# 1_P1.net
KiCad netlist of a schematic drawn in Altium Designer
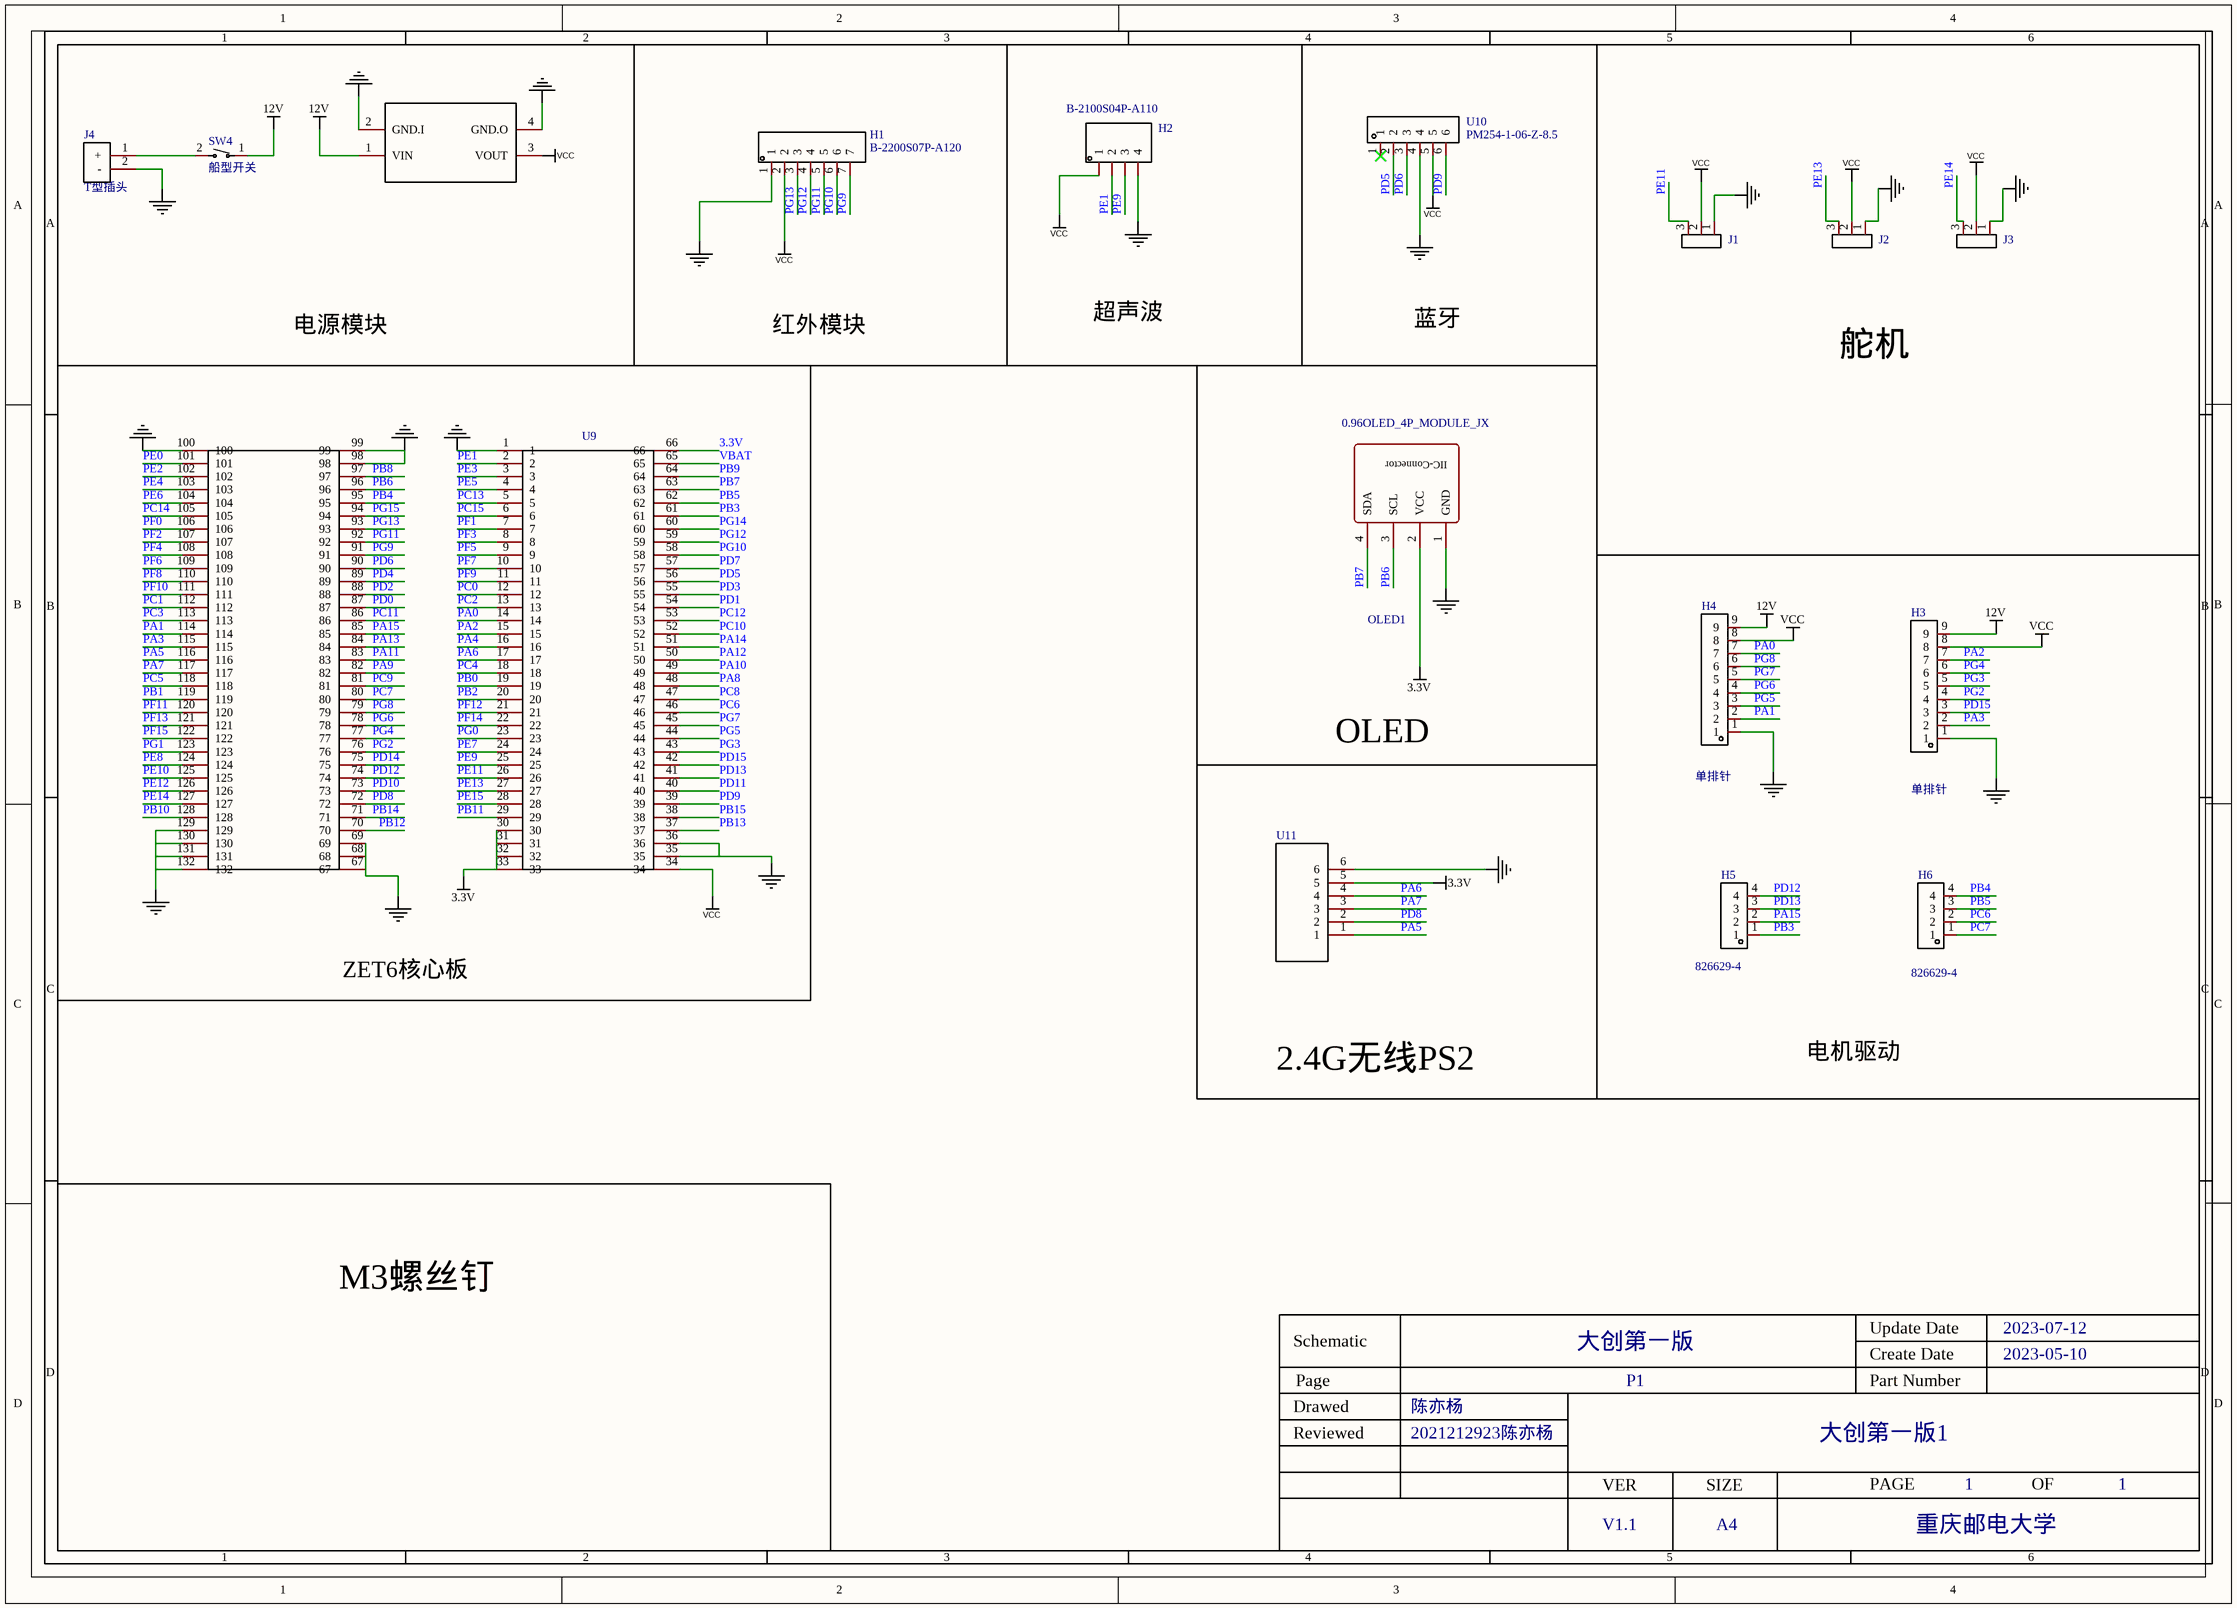
[diagram p0: 1_P1.schdoc]

(export (version "E")
  (design (tool "Eeschema 10.0.6"))
  (components
    (comp (ref "H1")
      (value "B-2200S07P-A120")
      (description "排数:单排;总孔位数:7;间距:2.54mm;插孔结构:1x7P;行距:-;安装类型:直插;塑高:-;触头材质:黄铜;触头镀层:-;")
      (fields (field (name "NAME") "B-2200S07P-A120") (field (name "MANUFACTURER") "Ckmtw(灿科盟)"))
      (libsource (lib "altium-import") (part "root_1_B-2200S07P-A120_"))
    )
    (comp (ref "H2")
      (value "B-2100S04P-A110")
      (fields (field (name "NAME") "B-2100S04P-A110") (field (name "MANUFACTURER") "Ckmtw(灿科盟)"))
      (libsource (lib "altium-import") (part "root_1_B-2100S04P-A110_"))
    )
    (comp (ref "H3")
      (value "单排针")
      (fields (field (name "NAME") "单排针"))
      (libsource (lib "altium-import") (part "root_2_排针9P-2.54MM直插_"))
    )
    (comp (ref "H4")
      (value "单排针")
      (fields (field (name "NAME") "单排针"))
      (libsource (lib "altium-import") (part "root_2_排针9P-2.54MM直插_"))
    )
    (comp (ref "H5")
      (value "826629-4")
      (fields (field (name "NAME") "826629-4") (field (name "MANUFACTURER") "TE Connectivity(美国泰科)"))
      (libsource (lib "altium-import") (part "root_2_排针2_"))
    )
    (comp (ref "H6")
      (value "826629-4")
      (fields (field (name "NAME") "826629-4") (field (name "MANUFACTURER") "TE Connectivity(美国泰科)"))
      (libsource (lib "altium-import") (part "root_2_排针2_"))
    )
    (comp (ref "J1") (value "3排针") (libsource (lib "altium-import") (part "root_2_3排针_")))
    (comp (ref "J2") (value "3排针") (libsource (lib "altium-import") (part "root_2_3排针_")))
    (comp (ref "J3") (value "3排针") (libsource (lib "altium-import") (part "root_2_3排针_")))
    (comp (ref "J4")
      (value "T型插头")
      (fields (field (name "NAME") "T型插头"))
      (libsource (lib "altium-import") (part "root_0_T型插头_"))
    )
    (comp (ref "OLED1")
      (value "0.96OLED_4P_MODULE_JX")
      (fields (field (name "NAME") "0.96OLED_4P_MODULE_JX"))
      (libsource (lib "altium-import") (part "root_3_0.96OLED_4P_MODULE_JX_"))
    )
    (comp (ref "SW4")
      (value "船型开关")
      (description "额定电流:6A;额定电压(AC):250V;额定电压(DC):-;电路结构:单刀双掷;致动器类型:凹面弯曲;致动器颜色:黑色;致动器标志:O-;照明颜色:-;端接样式:焊片;开关功能:开-关;")
      (fields (field (name "NAME") "船型开关") (field (name "MANUFACTURER") "HONGJU(宏聚)"))
      (libsource (lib "altium-import") (part "root_0_mirrored_MR1-110-C5N-BBAA_"))
    )
    (comp (ref "U6") (value "LM2596") (libsource (lib "altium-import") (part "root_0_LM2596_")))
    (comp (ref "U9")
      (value "ZET6核心板")
      (description "F103ZET6核心板")
      (libsource (lib "altium-import") (part "root_0_ZET6核心板_"))
    )
    (comp (ref "U10")
      (value "PM254-1-06-Z-8.5")
      (fields (field (name "NAME") "PM254-1-06-Z-8.5") (field (name "MANUFACTURER") "HCTL(华灿天禄)"))
      (libsource (lib "altium-import") (part "root_1_PM254-1-06-Z-8.5_"))
    )
    (comp (ref "U11") (value "排针1*6") (libsource (lib "altium-import") (part "root_2_排针1*6_")))
  )
  (nets
    (net (code "1") (name "/PA0") (class "Default")
      (node (ref "H4") (pin "7") (pinfunction "7_7") (pintype "passive"))
      (node (ref "U9") (pin "14") (pinfunction "14_14") (pintype "passive"))
    )
    (net (code "2") (name "/PA1") (class "Default")
      (node (ref "H4") (pin "2") (pinfunction "2_2") (pintype "passive"))
      (node (ref "U9") (pin "114") (pinfunction "114_114") (pintype "passive"))
    )
    (net (code "3") (name "/PA2") (class "Default")
      (node (ref "H3") (pin "7") (pinfunction "7_7") (pintype "passive"))
      (node (ref "U9") (pin "15") (pinfunction "15_15") (pintype "passive"))
    )
    (net (code "4") (name "/PA3") (class "Default")
      (node (ref "H3") (pin "2") (pinfunction "2_2") (pintype "passive"))
      (node (ref "U9") (pin "115") (pinfunction "115_115") (pintype "passive"))
    )
    (net (code "5") (name "/PA4") (class "Default")
      (node (ref "U9") (pin "16") (pinfunction "16_16") (pintype "passive"))
    )
    (net (code "6") (name "/PA5") (class "Default")
      (node (ref "U11") (pin "1") (pinfunction "1_1") (pintype "passive"))
      (node (ref "U9") (pin "116") (pinfunction "116_116") (pintype "passive"))
    )
    (net (code "7") (name "/PA6") (class "Default")
      (node (ref "U11") (pin "4") (pinfunction "4_4") (pintype "passive"))
      (node (ref "U9") (pin "17") (pinfunction "17_17") (pintype "passive"))
    )
    (net (code "8") (name "/PA7") (class "Default")
      (node (ref "U11") (pin "3") (pinfunction "3_3") (pintype "passive"))
      (node (ref "U9") (pin "117") (pinfunction "117_117") (pintype "passive"))
    )
    (net (code "9") (name "/PA8") (class "Default")
      (node (ref "U9") (pin "48") (pinfunction "48_48") (pintype "passive"))
    )
    (net (code "10") (name "/PA9") (class "Default")
      (node (ref "U9") (pin "82") (pinfunction "82_82") (pintype "passive"))
    )
    (net (code "11") (name "/PA10") (class "Default")
      (node (ref "U9") (pin "49") (pinfunction "49_49") (pintype "passive"))
    )
    (net (code "12") (name "/PA11") (class "Default")
      (node (ref "U9") (pin "83") (pinfunction "83_83") (pintype "passive"))
    )
    (net (code "13") (name "/PA12") (class "Default")
      (node (ref "U9") (pin "50") (pinfunction "50_50") (pintype "passive"))
    )
    (net (code "14") (name "/PA13") (class "Default")
      (node (ref "U9") (pin "84") (pinfunction "84_84") (pintype "passive"))
    )
    (net (code "15") (name "/PA14") (class "Default")
      (node (ref "U9") (pin "51") (pinfunction "51_51") (pintype "passive"))
    )
    (net (code "16") (name "/PA15") (class "Default")
      (node (ref "H5") (pin "2") (pinfunction "2_2") (pintype "passive"))
      (node (ref "U9") (pin "85") (pinfunction "85_85") (pintype "passive"))
    )
    (net (code "17") (name "/PB0") (class "Default")
      (node (ref "U9") (pin "19") (pinfunction "19_19") (pintype "passive"))
    )
    (net (code "18") (name "/PB1") (class "Default")
      (node (ref "U9") (pin "119") (pinfunction "119_119") (pintype "passive"))
    )
    (net (code "19") (name "/PB2") (class "Default")
      (node (ref "U9") (pin "20") (pinfunction "20_20") (pintype "passive"))
    )
    (net (code "20") (name "/PB3") (class "Default")
      (node (ref "H5") (pin "1") (pinfunction "1_1") (pintype "passive"))
      (node (ref "U9") (pin "61") (pinfunction "61_61") (pintype "passive"))
    )
    (net (code "21") (name "/PB4") (class "Default")
      (node (ref "H6") (pin "4") (pinfunction "4_4") (pintype "passive"))
      (node (ref "U9") (pin "95") (pinfunction "95_95") (pintype "passive"))
    )
    (net (code "22") (name "/PB5") (class "Default")
      (node (ref "H6") (pin "3") (pinfunction "3_3") (pintype "passive"))
      (node (ref "U9") (pin "62") (pinfunction "62_62") (pintype "passive"))
    )
    (net (code "23") (name "/PB6") (class "Default")
      (node (ref "OLED1") (pin "3") (pinfunction "SCL_3") (pintype "passive"))
      (node (ref "U9") (pin "96") (pinfunction "96_96") (pintype "passive"))
    )
    (net (code "24") (name "/PB7") (class "Default")
      (node (ref "OLED1") (pin "4") (pinfunction "SDA_4") (pintype "passive"))
      (node (ref "U9") (pin "63") (pinfunction "63_63") (pintype "passive"))
    )
    (net (code "25") (name "/PB8") (class "Default")
      (node (ref "U9") (pin "97") (pinfunction "97_97") (pintype "passive"))
    )
    (net (code "26") (name "/PB9") (class "Default")
      (node (ref "U9") (pin "64") (pinfunction "64_64") (pintype "passive"))
    )
    (net (code "27") (name "/PB10") (class "Default")
      (node (ref "U9") (pin "128") (pinfunction "128_128") (pintype "passive"))
    )
    (net (code "28") (name "/PB11") (class "Default")
      (node (ref "U9") (pin "29") (pinfunction "29_29") (pintype "passive"))
    )
    (net (code "29") (name "/PB12") (class "Default")
      (node (ref "U9") (pin "70") (pinfunction "70_70") (pintype "passive"))
    )
    (net (code "30") (name "/PB13") (class "Default")
      (node (ref "U9") (pin "37") (pinfunction "37_37") (pintype "passive"))
    )
    (net (code "31") (name "/PB14") (class "Default")
      (node (ref "U9") (pin "71") (pinfunction "71_71") (pintype "passive"))
    )
    (net (code "32") (name "/PB15") (class "Default")
      (node (ref "U9") (pin "38") (pinfunction "38_38") (pintype "passive"))
    )
    (net (code "33") (name "/PC0") (class "Default")
      (node (ref "U9") (pin "12") (pinfunction "12_12") (pintype "passive"))
    )
    (net (code "34") (name "/PC1") (class "Default")
      (node (ref "U9") (pin "112") (pinfunction "112_112") (pintype "passive"))
    )
    (net (code "35") (name "/PC2") (class "Default")
      (node (ref "U9") (pin "13") (pinfunction "13_13") (pintype "passive"))
    )
    (net (code "36") (name "/PC3") (class "Default")
      (node (ref "U9") (pin "113") (pinfunction "113_113") (pintype "passive"))
    )
    (net (code "37") (name "/PC4") (class "Default")
      (node (ref "U9") (pin "18") (pinfunction "18_18") (pintype "passive"))
    )
    (net (code "38") (name "/PC5") (class "Default")
      (node (ref "U9") (pin "118") (pinfunction "118_118") (pintype "passive"))
    )
    (net (code "39") (name "/PC6") (class "Default")
      (node (ref "H6") (pin "2") (pinfunction "2_2") (pintype "passive"))
      (node (ref "U9") (pin "46") (pinfunction "46_46") (pintype "passive"))
    )
    (net (code "40") (name "/PC7") (class "Default")
      (node (ref "H6") (pin "1") (pinfunction "1_1") (pintype "passive"))
      (node (ref "U9") (pin "80") (pinfunction "80_80") (pintype "passive"))
    )
    (net (code "41") (name "/PC8") (class "Default")
      (node (ref "U9") (pin "47") (pinfunction "47_47") (pintype "passive"))
    )
    (net (code "42") (name "/PC9") (class "Default")
      (node (ref "U9") (pin "81") (pinfunction "81_81") (pintype "passive"))
    )
    (net (code "43") (name "/PC10") (class "Default")
      (node (ref "U9") (pin "52") (pinfunction "52_52") (pintype "passive"))
    )
    (net (code "44") (name "/PC11") (class "Default")
      (node (ref "U9") (pin "86") (pinfunction "86_86") (pintype "passive"))
    )
    (net (code "45") (name "/PC12") (class "Default")
      (node (ref "U9") (pin "53") (pinfunction "53_53") (pintype "passive"))
    )
    (net (code "46") (name "/PC13") (class "Default")
      (node (ref "U9") (pin "5") (pinfunction "5_5") (pintype "passive"))
    )
    (net (code "47") (name "/PC14") (class "Default")
      (node (ref "U9") (pin "105") (pinfunction "105_105") (pintype "passive"))
    )
    (net (code "48") (name "/PC15") (class "Default")
      (node (ref "U9") (pin "6") (pinfunction "6_6") (pintype "passive"))
    )
    (net (code "49") (name "/PD0") (class "Default")
      (node (ref "U9") (pin "87") (pinfunction "87_87") (pintype "passive"))
    )
    (net (code "50") (name "/PD1") (class "Default")
      (node (ref "U9") (pin "54") (pinfunction "54_54") (pintype "passive"))
    )
    (net (code "51") (name "/PD2") (class "Default")
      (node (ref "U9") (pin "88") (pinfunction "88_88") (pintype "passive"))
    )
    (net (code "52") (name "/PD3") (class "Default")
      (node (ref "U9") (pin "55") (pinfunction "55_55") (pintype "passive"))
    )
    (net (code "53") (name "/PD4") (class "Default")
      (node (ref "U9") (pin "89") (pinfunction "89_89") (pintype "passive"))
    )
    (net (code "54") (name "/PD5") (class "Default")
      (node (ref "U10") (pin "2") (pinfunction "2_2") (pintype "passive"))
      (node (ref "U9") (pin "56") (pinfunction "56_56") (pintype "passive"))
    )
    (net (code "55") (name "/PD6") (class "Default")
      (node (ref "U10") (pin "3") (pinfunction "3_3") (pintype "passive"))
      (node (ref "U9") (pin "90") (pinfunction "90_90") (pintype "passive"))
    )
    (net (code "56") (name "/PD7") (class "Default")
      (node (ref "U9") (pin "57") (pinfunction "57_57") (pintype "passive"))
    )
    (net (code "57") (name "/PD8") (class "Default")
      (node (ref "U11") (pin "2") (pinfunction "2_2") (pintype "passive"))
      (node (ref "U9") (pin "72") (pinfunction "72_72") (pintype "passive"))
    )
    (net (code "58") (name "/PD9") (class "Default")
      (node (ref "U10") (pin "6") (pinfunction "6_6") (pintype "passive"))
      (node (ref "U9") (pin "39") (pinfunction "39_39") (pintype "passive"))
    )
    (net (code "59") (name "/PD10") (class "Default")
      (node (ref "U9") (pin "73") (pinfunction "73_73") (pintype "passive"))
    )
    (net (code "60") (name "/PD11") (class "Default")
      (node (ref "U9") (pin "40") (pinfunction "40_40") (pintype "passive"))
    )
    (net (code "61") (name "/PD12") (class "Default")
      (node (ref "H5") (pin "4") (pinfunction "4_4") (pintype "passive"))
      (node (ref "U9") (pin "74") (pinfunction "74_74") (pintype "passive"))
    )
    (net (code "62") (name "/PD13") (class "Default")
      (node (ref "H5") (pin "3") (pinfunction "3_3") (pintype "passive"))
      (node (ref "U9") (pin "41") (pinfunction "41_41") (pintype "passive"))
    )
    (net (code "63") (name "/PD14") (class "Default")
      (node (ref "U9") (pin "75") (pinfunction "75_75") (pintype "passive"))
    )
    (net (code "64") (name "/PD15") (class "Default")
      (node (ref "H3") (pin "3") (pinfunction "3_3") (pintype "passive"))
      (node (ref "U9") (pin "42") (pinfunction "42_42") (pintype "passive"))
    )
    (net (code "65") (name "/PE0") (class "Default")
      (node (ref "U9") (pin "101") (pinfunction "101_101") (pintype "passive"))
    )
    (net (code "66") (name "/PE1") (class "Default")
      (node (ref "H2") (pin "2") (pinfunction "2_2") (pintype "passive"))
      (node (ref "U9") (pin "2") (pinfunction "2_2") (pintype "passive"))
    )
    (net (code "67") (name "/PE2") (class "Default")
      (node (ref "U9") (pin "102") (pinfunction "102_102") (pintype "passive"))
    )
    (net (code "68") (name "/PE3") (class "Default")
      (node (ref "U9") (pin "3") (pinfunction "3_3") (pintype "passive"))
    )
    (net (code "69") (name "/PE4") (class "Default")
      (node (ref "U9") (pin "103") (pinfunction "103_103") (pintype "passive"))
    )
    (net (code "70") (name "/PE5") (class "Default")
      (node (ref "U9") (pin "4") (pinfunction "4_4") (pintype "passive"))
    )
    (net (code "71") (name "/PE6") (class "Default")
      (node (ref "U9") (pin "104") (pinfunction "104_104") (pintype "passive"))
    )
    (net (code "72") (name "/PE7") (class "Default")
      (node (ref "U9") (pin "24") (pinfunction "24_24") (pintype "passive"))
    )
    (net (code "73") (name "/PE8") (class "Default")
      (node (ref "U9") (pin "124") (pinfunction "124_124") (pintype "passive"))
    )
    (net (code "74") (name "/PE9") (class "Default")
      (node (ref "H2") (pin "3") (pinfunction "3_3") (pintype "passive"))
      (node (ref "U9") (pin "25") (pinfunction "25_25") (pintype "passive"))
    )
    (net (code "75") (name "/PE10") (class "Default")
      (node (ref "U9") (pin "125") (pinfunction "125_125") (pintype "passive"))
    )
    (net (code "76") (name "/PE11") (class "Default")
      (node (ref "J1") (pin "3") (pinfunction "3_3") (pintype "passive"))
      (node (ref "U9") (pin "26") (pinfunction "26_26") (pintype "passive"))
    )
    (net (code "77") (name "/PE12") (class "Default")
      (node (ref "U9") (pin "126") (pinfunction "126_126") (pintype "passive"))
    )
    (net (code "78") (name "/PE13") (class "Default")
      (node (ref "J2") (pin "3") (pinfunction "3_3") (pintype "passive"))
      (node (ref "U9") (pin "27") (pinfunction "27_27") (pintype "passive"))
    )
    (net (code "79") (name "/PE14") (class "Default")
      (node (ref "J3") (pin "3") (pinfunction "3_3") (pintype "passive"))
      (node (ref "U9") (pin "127") (pinfunction "127_127") (pintype "passive"))
    )
    (net (code "80") (name "/PE15") (class "Default")
      (node (ref "U9") (pin "28") (pinfunction "28_28") (pintype "passive"))
    )
    (net (code "81") (name "/PF0") (class "Default")
      (node (ref "U9") (pin "106") (pinfunction "106_106") (pintype "passive"))
    )
    (net (code "82") (name "/PF1") (class "Default")
      (node (ref "U9") (pin "7") (pinfunction "7_7") (pintype "passive"))
    )
    (net (code "83") (name "/PF2") (class "Default")
      (node (ref "U9") (pin "107") (pinfunction "107_107") (pintype "passive"))
    )
    (net (code "84") (name "/PF3") (class "Default")
      (node (ref "U9") (pin "8") (pinfunction "8_8") (pintype "passive"))
    )
    (net (code "85") (name "/PF4") (class "Default")
      (node (ref "U9") (pin "108") (pinfunction "108_108") (pintype "passive"))
    )
    (net (code "86") (name "/PF5") (class "Default")
      (node (ref "U9") (pin "9") (pinfunction "9_9") (pintype "passive"))
    )
    (net (code "87") (name "/PF6") (class "Default")
      (node (ref "U9") (pin "109") (pinfunction "109_109") (pintype "passive"))
    )
    (net (code "88") (name "/PF7") (class "Default")
      (node (ref "U9") (pin "10") (pinfunction "10_10") (pintype "passive"))
    )
    (net (code "89") (name "/PF8") (class "Default")
      (node (ref "U9") (pin "110") (pinfunction "110_110") (pintype "passive"))
    )
    (net (code "90") (name "/PF9") (class "Default")
      (node (ref "U9") (pin "11") (pinfunction "11_11") (pintype "passive"))
    )
    (net (code "91") (name "/PF10") (class "Default")
      (node (ref "U9") (pin "111") (pinfunction "111_111") (pintype "passive"))
    )
    (net (code "92") (name "/PF11") (class "Default")
      (node (ref "U9") (pin "120") (pinfunction "120_120") (pintype "passive"))
    )
    (net (code "93") (name "/PF12") (class "Default")
      (node (ref "U9") (pin "21") (pinfunction "21_21") (pintype "passive"))
    )
    (net (code "94") (name "/PF13") (class "Default")
      (node (ref "U9") (pin "121") (pinfunction "121_121") (pintype "passive"))
    )
    (net (code "95") (name "/PF14") (class "Default")
      (node (ref "U9") (pin "22") (pinfunction "22_22") (pintype "passive"))
    )
    (net (code "96") (name "/PF15") (class "Default")
      (node (ref "U9") (pin "122") (pinfunction "122_122") (pintype "passive"))
    )
    (net (code "97") (name "/PG0") (class "Default")
      (node (ref "U9") (pin "23") (pinfunction "23_23") (pintype "passive"))
    )
    (net (code "98") (name "/PG1") (class "Default")
      (node (ref "U9") (pin "123") (pinfunction "123_123") (pintype "passive"))
    )
    (net (code "99") (name "/PG2") (class "Default")
      (node (ref "H3") (pin "4") (pinfunction "4_4") (pintype "passive"))
      (node (ref "U9") (pin "76") (pinfunction "76_76") (pintype "passive"))
    )
    (net (code "100") (name "/PG3") (class "Default")
      (node (ref "H3") (pin "5") (pinfunction "5_5") (pintype "passive"))
      (node (ref "U9") (pin "43") (pinfunction "43_43") (pintype "passive"))
    )
    (net (code "101") (name "/PG4") (class "Default")
      (node (ref "H3") (pin "6") (pinfunction "6_6") (pintype "passive"))
      (node (ref "U9") (pin "77") (pinfunction "77_77") (pintype "passive"))
    )
    (net (code "102") (name "/PG5") (class "Default")
      (node (ref "H4") (pin "3") (pinfunction "3_3") (pintype "passive"))
      (node (ref "U9") (pin "44") (pinfunction "44_44") (pintype "passive"))
    )
    (net (code "103") (name "/PG6") (class "Default")
      (node (ref "H4") (pin "4") (pinfunction "4_4") (pintype "passive"))
      (node (ref "U9") (pin "78") (pinfunction "78_78") (pintype "passive"))
    )
    (net (code "104") (name "/PG7") (class "Default")
      (node (ref "H4") (pin "5") (pinfunction "5_5") (pintype "passive"))
      (node (ref "U9") (pin "45") (pinfunction "45_45") (pintype "passive"))
    )
    (net (code "105") (name "/PG8") (class "Default")
      (node (ref "H4") (pin "6") (pinfunction "6_6") (pintype "passive"))
      (node (ref "U9") (pin "79") (pinfunction "79_79") (pintype "passive"))
    )
    (net (code "106") (name "/PG9") (class "Default")
      (node (ref "H1") (pin "7") (pinfunction "7_7") (pintype "passive"))
      (node (ref "U9") (pin "91") (pinfunction "91_91") (pintype "passive"))
    )
    (net (code "107") (name "/PG10") (class "Default")
      (node (ref "H1") (pin "6") (pinfunction "6_6") (pintype "passive"))
      (node (ref "U9") (pin "58") (pinfunction "58_58") (pintype "passive"))
    )
    (net (code "108") (name "/PG11") (class "Default")
      (node (ref "H1") (pin "5") (pinfunction "5_5") (pintype "passive"))
      (node (ref "U9") (pin "92") (pinfunction "92_92") (pintype "passive"))
    )
    (net (code "109") (name "/PG12") (class "Default")
      (node (ref "H1") (pin "4") (pinfunction "4_4") (pintype "passive"))
      (node (ref "U9") (pin "59") (pinfunction "59_59") (pintype "passive"))
    )
    (net (code "110") (name "/PG13") (class "Default")
      (node (ref "H1") (pin "3") (pinfunction "3_3") (pintype "passive"))
      (node (ref "U9") (pin "93") (pinfunction "93_93") (pintype "passive"))
    )
    (net (code "111") (name "/PG14") (class "Default")
      (node (ref "U9") (pin "60") (pinfunction "60_60") (pintype "passive"))
    )
    (net (code "112") (name "/PG15") (class "Default")
      (node (ref "U9") (pin "94") (pinfunction "94_94") (pintype "passive"))
    )
    (net (code "113") (name "/VBAT") (class "Default")
      (node (ref "U9") (pin "65") (pinfunction "65_65") (pintype "passive"))
    )
    (net (code "114") (name "3.3V") (class "Default")
      (node (ref "OLED1") (pin "2") (pinfunction "VCC_2") (pintype "passive"))
      (node (ref "U11") (pin "5") (pinfunction "5_5") (pintype "passive"))
      (node (ref "U9") (pin "30") (pinfunction "30_30") (pintype "passive"))
      (node (ref "U9") (pin "31") (pinfunction "31_31") (pintype "passive"))
      (node (ref "U9") (pin "32") (pinfunction "32_32") (pintype "passive"))
      (node (ref "U9") (pin "33") (pinfunction "33_33") (pintype "passive"))
      (node (ref "U9") (pin "66") (pinfunction "66_66") (pintype "passive"))
    )
    (net (code "115") (name "12V") (class "Default")
      (node (ref "H3") (pin "9") (pinfunction "9_9") (pintype "passive"))
      (node (ref "H4") (pin "9") (pinfunction "9_9") (pintype "passive"))
      (node (ref "SW4") (pin "1") (pinfunction "1_1") (pintype "passive"))
      (node (ref "U6") (pin "1") (pinfunction "VIN_1") (pintype "passive"))
    )
    (net (code "116") (name "<NO NET>") (class "Default")
      (node (ref "U11") (pin "6") (pinfunction "6_6") (pintype "passive"))
      (node (ref "U9") (pin "129") (pinfunction "129_129") (pintype "passive"))
      (node (ref "U9") (pin "130") (pinfunction "130_130") (pintype "passive"))
      (node (ref "U9") (pin "131") (pinfunction "131_131") (pintype "passive"))
      (node (ref "U9") (pin "132") (pinfunction "132_132") (pintype "passive"))
      (node (ref "U9") (pin "35") (pinfunction "35_35") (pintype "passive"))
      (node (ref "U9") (pin "36") (pinfunction "36_36") (pintype "passive"))
      (node (ref "U9") (pin "67") (pinfunction "67_67") (pintype "passive"))
      (node (ref "U9") (pin "68") (pinfunction "68_68") (pintype "passive"))
      (node (ref "U9") (pin "69") (pinfunction "69_69") (pintype "passive"))
    )
    (net (code "117") (name "GND") (class "Default")
      (node (ref "H1") (pin "1") (pinfunction "1_1") (pintype "passive"))
      (node (ref "H2") (pin "4") (pinfunction "4_4") (pintype "passive"))
      (node (ref "H3") (pin "1") (pinfunction "1_1") (pintype "passive"))
      (node (ref "H4") (pin "1") (pinfunction "1_1") (pintype "passive"))
      (node (ref "J1") (pin "1") (pinfunction "1_1") (pintype "passive"))
      (node (ref "J2") (pin "1") (pinfunction "1_1") (pintype "passive"))
      (node (ref "J3") (pin "1") (pinfunction "1_1") (pintype "passive"))
      (node (ref "J4") (pin "2") (pinfunction "-_2") (pintype "passive"))
      (node (ref "OLED1") (pin "1") (pinfunction "GND_1") (pintype "passive"))
      (node (ref "U10") (pin "4") (pinfunction "4_4") (pintype "passive"))
      (node (ref "U6") (pin "2") (pinfunction "GND.I_2") (pintype "passive"))
      (node (ref "U6") (pin "4") (pinfunction "GND.O_4") (pintype "passive"))
      (node (ref "U9") (pin "1") (pinfunction "1_1") (pintype "passive"))
      (node (ref "U9") (pin "100") (pinfunction "100_100") (pintype "passive"))
      (node (ref "U9") (pin "98") (pinfunction "98_98") (pintype "passive"))
      (node (ref "U9") (pin "99") (pinfunction "99_99") (pintype "passive"))
    )
    (net (code "118") (name "Net-(J4-+)") (class "Default")
      (node (ref "J4") (pin "1") (pinfunction "+_1") (pintype "passive"))
      (node (ref "SW4") (pin "2") (pinfunction "2_2") (pintype "passive"))
    )
    (net (code "119") (name "VCC") (class "Default")
      (node (ref "H1") (pin "2") (pinfunction "2_2") (pintype "passive"))
      (node (ref "H2") (pin "1") (pinfunction "1_1") (pintype "passive"))
      (node (ref "H3") (pin "8") (pinfunction "8_8") (pintype "passive"))
      (node (ref "H4") (pin "8") (pinfunction "8_8") (pintype "passive"))
      (node (ref "J1") (pin "2") (pinfunction "2_2") (pintype "passive"))
      (node (ref "J2") (pin "2") (pinfunction "2_2") (pintype "passive"))
      (node (ref "J3") (pin "2") (pinfunction "2_2") (pintype "passive"))
      (node (ref "U10") (pin "5") (pinfunction "5_5") (pintype "passive"))
      (node (ref "U6") (pin "3") (pinfunction "VOUT_3") (pintype "passive"))
      (node (ref "U9") (pin "34") (pinfunction "34_34") (pintype "passive"))
    )
    (net (code "120") (name "unconnected-(U10-Pad1)") (class "Default")
      (node (ref "U10") (pin "1") (pinfunction "1_1") (pintype "passive+no_connect"))
    )
  )
)
